# Sheet1.net
KiCad netlist of a schematic drawn in Altium Designer
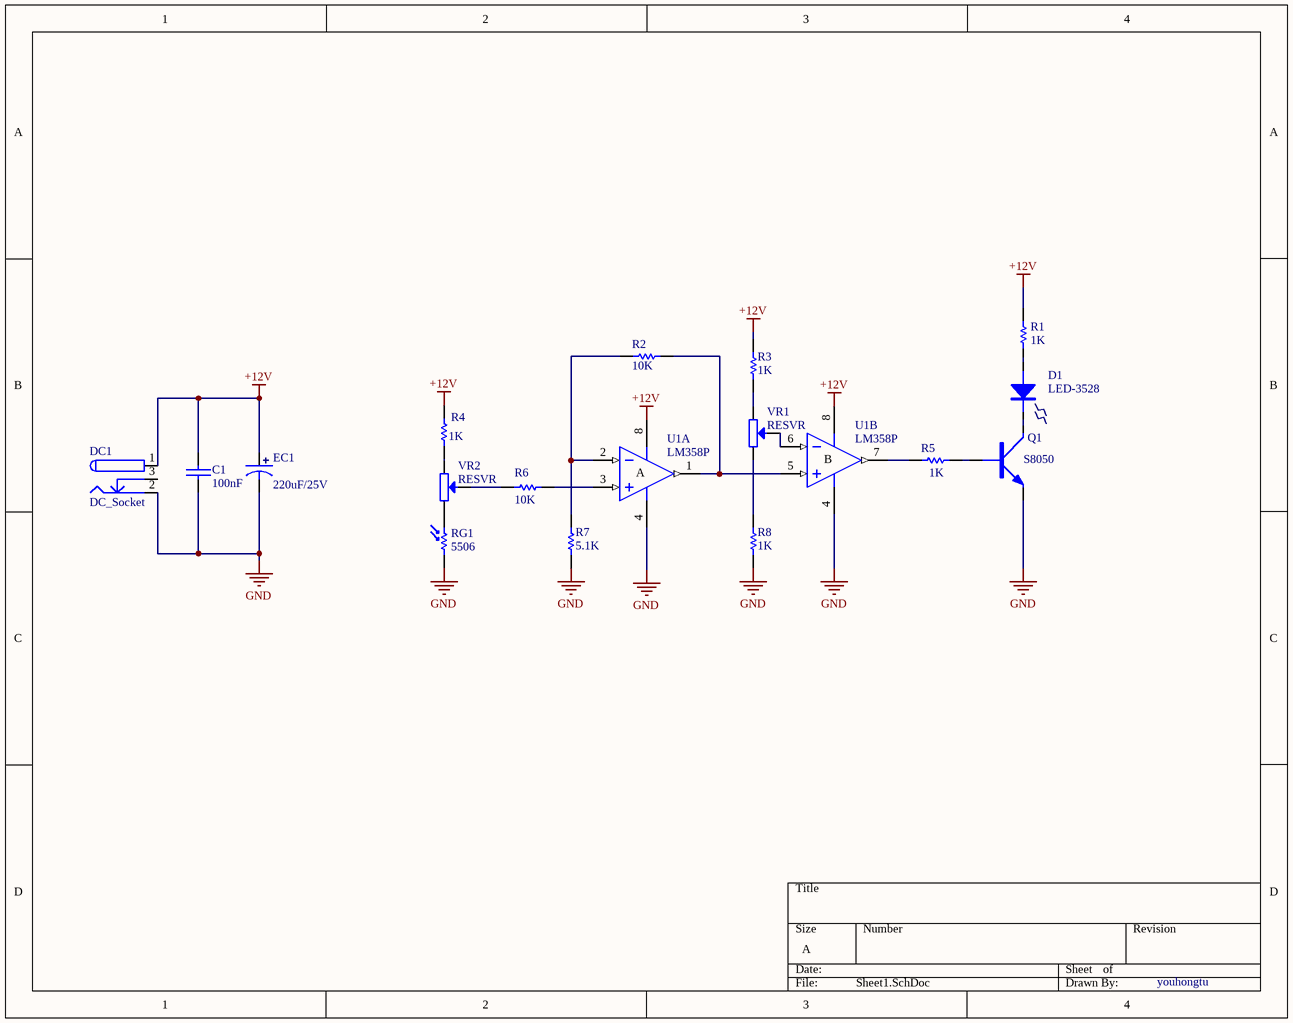
[diagram p0: Sheet1.SchDoc]

(export (version "E")
  (design (tool "Eeschema 10.0.6"))
  (components
    (comp (ref "C1")
      (value "100nF")
      (footprint "RAD-0.2")
      (description "无极性电容")
      (libsource (lib "电容") (part "CAP"))
    )
    (comp (ref "D1") (value "LED-3528") (footprint "LED3-RED") (libsource (lib "LED") (part "LED-3528")))
    (comp (ref "DC1") (value "DC_Socket") (footprint "DC-005") (libsource (lib "电源插座") (part "DC_Socket")))
    (comp (ref "EC1")
      (value "220uF/25V")
      (footprint "DIP-EC3.5X8X11.5")
      (description "直插电解电容")
      (libsource (lib "电容") (part "DIP_ECAP"))
    )
    (comp (ref "Q1")
      (value "S8050")
      (footprint "TO-92A")
      (description "NPN三极管")
      (libsource (lib "三极管") (part "NPN"))
    )
    (comp (ref "R1") (value "1K") (footprint "AXIAL0.4") (libsource (lib "电阻") (part "RES")))
    (comp (ref "R2") (value "10K") (footprint "AXIAL0.4") (libsource (lib "电阻") (part "RES")))
    (comp (ref "R3") (value "1K") (footprint "AXIAL0.4") (libsource (lib "电阻") (part "RES")))
    (comp (ref "R4") (value "1K") (footprint "AXIAL0.4") (libsource (lib "电阻") (part "RES")))
    (comp (ref "R5") (value "1K") (footprint "AXIAL0.4") (libsource (lib "电阻") (part "RES")))
    (comp (ref "R6") (value "10K") (footprint "AXIAL0.4") (libsource (lib "电阻") (part "RES")))
    (comp (ref "R7") (value "5.1K") (footprint "AXIAL0.4") (libsource (lib "电阻") (part "RES")))
    (comp (ref "R8") (value "1K") (footprint "AXIAL0.4") (libsource (lib "电阻") (part "RES")))
    (comp (ref "RG1")
      (value "5506")
      (footprint "Photoresistor")
      (description "光敏电阻")
      (libsource (lib "电阻") (part "Photoresistor"))
    )
    (comp (ref "U1")
      (value "LM358P")
      (footprint "P008")
      (description "Dual Operational Amplifier")
      (fields (field (name "PUBLISHER") "Altium Limited"))
      (libsource (lib "TI Operational Amplifier") (part "LM358P"))
    )
    (comp (ref "VR1") (value "RESVR") (footprint "3296W") (libsource (lib "电阻") (part "RESVR")))
    (comp (ref "VR2") (value "RESVR") (footprint "3296W") (libsource (lib "电阻") (part "RESVR")))
  )
  (nets
    (net (code "1") (name "+12V") (class "Default")
      (node (ref "C1") (pin "2") (pinfunction "2_2") (pintype "passive"))
      (node (ref "DC1") (pin "1") (pinfunction "1_1") (pintype "power_in"))
      (node (ref "EC1") (pin "1") (pinfunction "1_1") (pintype "passive"))
      (node (ref "R1") (pin "2") (pinfunction "2_2") (pintype "passive"))
      (node (ref "R3") (pin "2") (pinfunction "2_2") (pintype "passive"))
      (node (ref "R4") (pin "2") (pinfunction "2_2") (pintype "passive"))
      (node (ref "U1") (pin "8") (pinfunction "V+_8") (pintype "power_in"))
    )
    (net (code "2") (name "GND") (class "Default")
      (node (ref "C1") (pin "1") (pinfunction "1_1") (pintype "passive"))
      (node (ref "DC1") (pin "2") (pinfunction "2_2") (pintype "power_in"))
      (node (ref "EC1") (pin "2") (pinfunction "2_2") (pintype "passive"))
      (node (ref "Q1") (pin "E") (pinfunction "E_E") (pintype "passive"))
      (node (ref "R7") (pin "1") (pinfunction "1_1") (pintype "passive"))
      (node (ref "R8") (pin "1") (pinfunction "1_1") (pintype "passive"))
      (node (ref "RG1") (pin "1") (pinfunction "1_1") (pintype "passive"))
      (node (ref "U1") (pin "4") (pinfunction "V-_4") (pintype "power_in"))
    )
    (net (code "3") (name "Net-(D1-PadA)") (class "Default")
      (node (ref "D1") (pin "A") (pinfunction "A_A") (pintype "passive"))
      (node (ref "R1") (pin "1") (pinfunction "1_1") (pintype "passive"))
    )
    (net (code "4") (name "Net-(D1-PadK)") (class "Default")
      (node (ref "D1") (pin "K") (pinfunction "K_K") (pintype "passive"))
      (node (ref "Q1") (pin "C") (pinfunction "C_C") (pintype "passive"))
    )
    (net (code "5") (name "Net-(Q1-PadB)") (class "Default")
      (node (ref "Q1") (pin "B") (pinfunction "B_B") (pintype "passive"))
      (node (ref "R5") (pin "2") (pinfunction "2_2") (pintype "passive"))
    )
    (net (code "6") (name "Net-(R3-Pad1)") (class "Default")
      (node (ref "R3") (pin "1") (pinfunction "1_1") (pintype "passive"))
      (node (ref "VR1") (pin "1") (pinfunction "1_1") (pintype "passive"))
    )
    (net (code "7") (name "Net-(R4-Pad1)") (class "Default")
      (node (ref "R4") (pin "1") (pinfunction "1_1") (pintype "passive"))
      (node (ref "VR2") (pin "1") (pinfunction "1_1") (pintype "passive"))
    )
    (net (code "8") (name "Net-(R6-Pad2)") (class "Default")
      (node (ref "R6") (pin "2") (pinfunction "2_2") (pintype "passive"))
      (node (ref "VR2") (pin "3") (pinfunction "3_3") (pintype "passive"))
    )
    (net (code "9") (name "Net-(R8-Pad2)") (class "Default")
      (node (ref "R8") (pin "2") (pinfunction "2_2") (pintype "passive"))
      (node (ref "VR1") (pin "2") (pinfunction "2_2") (pintype "passive"))
    )
    (net (code "10") (name "Net-(RG1-Pad2)") (class "Default")
      (node (ref "RG1") (pin "2") (pinfunction "2_2") (pintype "passive"))
      (node (ref "VR2") (pin "2") (pinfunction "2_2") (pintype "passive"))
    )
    (net (code "11") (name "Net-(U1A-IN+)") (class "Default")
      (node (ref "R6") (pin "1") (pinfunction "1_1") (pintype "passive"))
      (node (ref "U1") (pin "3") (pinfunction "IN+_3") (pintype "input"))
    )
    (net (code "12") (name "Net-(U1A-IN-)") (class "Default")
      (node (ref "R2") (pin "2") (pinfunction "2_2") (pintype "passive"))
      (node (ref "R7") (pin "2") (pinfunction "2_2") (pintype "passive"))
      (node (ref "U1") (pin "2") (pinfunction "IN-_2") (pintype "input"))
    )
    (net (code "13") (name "Net-(U1A-OUT)") (class "Default")
      (node (ref "R2") (pin "1") (pinfunction "1_1") (pintype "passive"))
      (node (ref "U1") (pin "1") (pinfunction "OUT_1") (pintype "output"))
      (node (ref "U1") (pin "5") (pinfunction "IN+_5") (pintype "input"))
    )
    (net (code "14") (name "Net-(U1B-IN-)") (class "Default")
      (node (ref "U1") (pin "6") (pinfunction "IN-_6") (pintype "input"))
      (node (ref "VR1") (pin "3") (pinfunction "3_3") (pintype "passive"))
    )
    (net (code "15") (name "Net-(U1B-OUT)") (class "Default")
      (node (ref "R5") (pin "1") (pinfunction "1_1") (pintype "passive"))
      (node (ref "U1") (pin "7") (pinfunction "OUT_7") (pintype "output"))
    )
    (net (code "16") (name "unconnected-(DC1-Pad3)") (class "Default")
      (node (ref "DC1") (pin "3") (pinfunction "3_3") (pintype "power_in"))
    )
  )
)
